# EP_project_Receiver.net
KiCad netlist of a schematic drawn in EAGLE
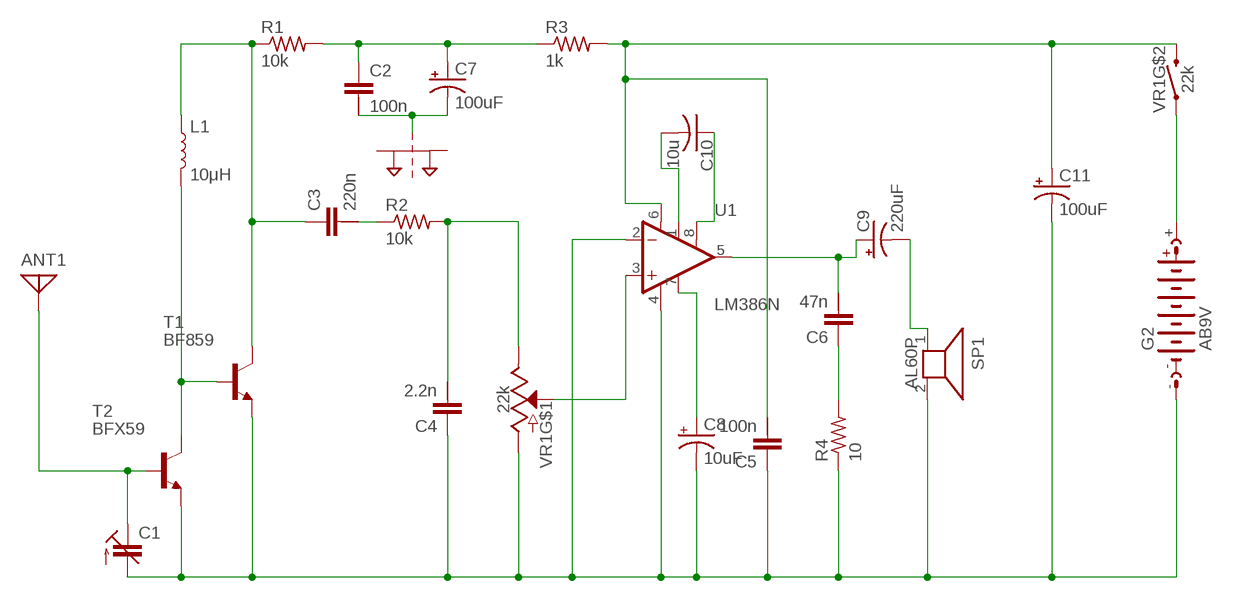
[diagram p0: schematic, sheet 1]

(export (version "E")
  (design (tool "Eeschema 10.0.6"))
  (components
    (comp (ref "ANT1")
      (value "ANTENNA")
      (footprint "eagle-import:PAD-01")
      (libsource (lib "eagle-import") (part "ANTENNA"))
    )
    (comp (ref "C1")
      (value "C-TRIMM808")
      (footprint "eagle-import:CTRIM808-BC")
      (libsource (lib "eagle-import") (part "C-TRIMM808"))
    )
    (comp (ref "C2")
      (value "100n")
      (footprint "eagle-import:C2.5_5-5")
      (libsource (lib "eagle-import") (part "C-2.5-5/5"))
    )
    (comp (ref "C3")
      (value "220n")
      (footprint "eagle-import:C2.5_5-5")
      (libsource (lib "eagle-import") (part "C-2.5-5/5"))
    )
    (comp (ref "C4")
      (value "2.2n")
      (footprint "eagle-import:C2.5_5-5")
      (libsource (lib "eagle-import") (part "C-2.5-5/5"))
    )
    (comp (ref "C5")
      (value "100n")
      (footprint "eagle-import:C2.5_5-5")
      (libsource (lib "eagle-import") (part "C-2.5-5/5"))
    )
    (comp (ref "C6")
      (value "47n")
      (footprint "eagle-import:C2.5_5-5")
      (libsource (lib "eagle-import") (part "C-2.5-5/5"))
    )
    (comp (ref "C7")
      (value "100uF")
      (footprint "eagle-import:PANASONIC_G")
      (libsource (lib "eagle-import") (part "560UF-PANASONIC_G-25V-20%"))
    )
    (comp (ref "C8")
      (value "10uF")
      (footprint "eagle-import:PANASONIC_G")
      (libsource (lib "eagle-import") (part "560UF-PANASONIC_G-25V-20%"))
    )
    (comp (ref "C9")
      (value "220uF")
      (footprint "eagle-import:PANASONIC_G")
      (libsource (lib "eagle-import") (part "560UF-PANASONIC_G-25V-20%"))
    )
    (comp (ref "C10")
      (value "10u")
      (footprint "eagle-import:C025-024X044")
      (libsource (lib "eagle-import") (part "C-US025-024X044"))
    )
    (comp (ref "C11")
      (value "100uF")
      (footprint "eagle-import:PANASONIC_G")
      (libsource (lib "eagle-import") (part "560UF-PANASONIC_G-25V-20%"))
    )
    (comp (ref "G2")
      (value "AB9V")
      (footprint "eagle-import:AB9V")
      (libsource (lib "eagle-import") (part "AB9V"))
    )
    (comp (ref "L1")
      (value "10μH")
      (footprint "eagle-import:0805")
      (libsource (lib "eagle-import") (part "10μH_SHIELDED_INDUCTOR0805"))
    )
    (comp (ref "R1")
      (value "10k")
      (footprint "eagle-import:0204_7")
      (libsource (lib "eagle-import") (part "R-US_0204/7"))
    )
    (comp (ref "R2")
      (value "10k")
      (footprint "eagle-import:0204_7")
      (libsource (lib "eagle-import") (part "R-US_0204/7"))
    )
    (comp (ref "R3")
      (value "1k")
      (footprint "eagle-import:0204_7")
      (libsource (lib "eagle-import") (part "R-US_0204/7"))
    )
    (comp (ref "R4")
      (value "10")
      (footprint "eagle-import:0204_7")
      (libsource (lib "eagle-import") (part "R-US_0204/7"))
    )
    (comp (ref "SP1")
      (value "AL60P")
      (footprint "eagle-import:AL60P")
      (libsource (lib "eagle-import") (part "AL60P"))
    )
    (comp (ref "SUPPLYTIE1")
      (value "2PT_GND_TIE")
      (footprint "eagle-import:2PT_GND_TIE")
      (libsource (lib "eagle-import") (part "2PT_GND_TIE"))
    )
    (comp (ref "T1")
      (value "BF859")
      (footprint "eagle-import:TO202")
      (libsource (lib "eagle-import") (part "BF859"))
    )
    (comp (ref "T2")
      (value "BFX59")
      (footprint "eagle-import:TO72")
      (libsource (lib "eagle-import") (part "BFX59"))
    )
    (comp (ref "U1")
      (value "LM386N")
      (footprint "eagle-import:DIP08")
      (libsource (lib "eagle-import") (part "LM386"))
    )
    (comp (ref "VR1")
      (value "22k")
      (footprint "eagle-import:POT-SWITCH-PTH")
      (libsource (lib "eagle-import") (part "POTENTIOMETER_W/SWITCHPOT_PTH_SWITCH"))
    )
  )
  (nets
    (net (code "1") (name "Net-(C1-A)") (class "Default")
      (node (ref "C1") (pin "2") (pinfunction "A_2") (pintype "passive"))
      (node (ref "C11") (pin "-") (pinfunction "-_-") (pintype "passive"))
      (node (ref "C4") (pin "1") (pinfunction "1_1") (pintype "passive"))
      (node (ref "C5") (pin "1") (pinfunction "1_1") (pintype "passive"))
      (node (ref "C8") (pin "-") (pinfunction "-_-") (pintype "passive"))
      (node (ref "G2") (pin "-") (pinfunction "-_-") (pintype "passive"))
      (node (ref "R4") (pin "1") (pinfunction "1_1") (pintype "passive"))
      (node (ref "SP1") (pin "2") (pinfunction "2_2") (pintype "passive"))
      (node (ref "T1") (pin "1") (pinfunction "E_1") (pintype "passive"))
      (node (ref "T2") (pin "1") (pinfunction "E_1") (pintype "passive"))
      (node (ref "U1") (pin "2") (pinfunction "-IN_2") (pintype "input"))
      (node (ref "U1") (pin "4") (pinfunction "V-_4") (pintype "power_in"))
      (node (ref "VR1") (pin "1") (pinfunction "A_1") (pintype "passive"))
    )
    (net (code "2") (name "Net-(C1-E)") (class "Default")
      (node (ref "ANT1") (pin "1") (pinfunction "1_1") (pintype "output"))
      (node (ref "C1") (pin "1") (pinfunction "E_1") (pintype "passive"))
      (node (ref "T2") (pin "2") (pinfunction "B_2") (pintype "passive"))
    )
    (net (code "3") (name "Net-(C2-Pad1)") (class "Default")
      (node (ref "C2") (pin "1") (pinfunction "1_1") (pintype "passive"))
      (node (ref "C7") (pin "+") (pinfunction "+_+") (pintype "passive"))
      (node (ref "R1") (pin "2") (pinfunction "2_2") (pintype "passive"))
      (node (ref "R3") (pin "1") (pinfunction "1_1") (pintype "passive"))
    )
    (net (code "4") (name "Net-(C2-Pad2)") (class "Default")
      (node (ref "C2") (pin "2") (pinfunction "2_2") (pintype "passive"))
      (node (ref "C7") (pin "-") (pinfunction "-_-") (pintype "passive"))
    )
    (net (code "5") (name "Net-(C3-Pad2)") (class "Default")
      (node (ref "C3") (pin "2") (pinfunction "2_2") (pintype "passive"))
      (node (ref "R2") (pin "1") (pinfunction "1_1") (pintype "passive"))
    )
    (net (code "6") (name "Net-(C6-Pad1)") (class "Default")
      (node (ref "C6") (pin "1") (pinfunction "1_1") (pintype "passive"))
      (node (ref "R4") (pin "2") (pinfunction "2_2") (pintype "passive"))
    )
    (net (code "7") (name "Net-(C9-Pad-)") (class "Default")
      (node (ref "C9") (pin "-") (pinfunction "-_-") (pintype "passive"))
      (node (ref "SP1") (pin "1") (pinfunction "1_1") (pintype "passive"))
    )
    (net (code "8") (name "Net-(C10-Pad1)") (class "Default")
      (node (ref "C10") (pin "1") (pinfunction "1_1") (pintype "passive"))
      (node (ref "U1") (pin "8") (pinfunction "GAIN_8") (pintype "bidirectional"))
    )
    (net (code "9") (name "Net-(C10-Pad2)") (class "Default")
      (node (ref "C10") (pin "2") (pinfunction "2_2") (pintype "passive"))
      (node (ref "U1") (pin "1") (pinfunction "GAIN_1") (pintype "bidirectional"))
    )
    (net (code "10") (name "Net-(T1-B)") (class "Default")
      (node (ref "L1") (pin "2") (pinfunction "2_2") (pintype "passive"))
      (node (ref "T1") (pin "3") (pinfunction "B_3") (pintype "passive"))
      (node (ref "T2") (pin "3") (pinfunction "C_3") (pintype "passive"))
    )
    (net (code "11") (name "Net-(T1-C)") (class "Default")
      (node (ref "C3") (pin "1") (pinfunction "1_1") (pintype "passive"))
      (node (ref "L1") (pin "1") (pinfunction "1_1") (pintype "passive"))
      (node (ref "R1") (pin "1") (pinfunction "1_1") (pintype "passive"))
      (node (ref "T1") (pin "2") (pinfunction "C_2") (pintype "passive"))
    )
    (net (code "12") (name "Net-(U1-+IN)") (class "Default")
      (node (ref "U1") (pin "3") (pinfunction "+IN_3") (pintype "input"))
      (node (ref "VR1") (pin "2") (pinfunction "S_2") (pintype "passive"))
    )
    (net (code "13") (name "Net-(U1-BP)") (class "Default")
      (node (ref "C8") (pin "+") (pinfunction "+_+") (pintype "passive"))
      (node (ref "U1") (pin "7") (pinfunction "BP_7") (pintype "bidirectional"))
    )
    (net (code "14") (name "Net-(U1-OUT)") (class "Default")
      (node (ref "C6") (pin "2") (pinfunction "2_2") (pintype "passive"))
      (node (ref "C9") (pin "+") (pinfunction "+_+") (pintype "passive"))
      (node (ref "U1") (pin "5") (pinfunction "OUT_5") (pintype "output"))
    )
    (net (code "15") (name "Net-(U1-V+)") (class "Default")
      (node (ref "C11") (pin "+") (pinfunction "+_+") (pintype "passive"))
      (node (ref "C5") (pin "2") (pinfunction "2_2") (pintype "passive"))
      (node (ref "R3") (pin "2") (pinfunction "2_2") (pintype "passive"))
      (node (ref "U1") (pin "6") (pinfunction "V+_6") (pintype "power_in"))
      (node (ref "VR1") (pin "S2") (pinfunction "2_S2") (pintype "passive"))
    )
    (net (code "16") (name "Net-(VR1A-E)") (class "Default")
      (node (ref "C4") (pin "2") (pinfunction "2_2") (pintype "passive"))
      (node (ref "R2") (pin "2") (pinfunction "2_2") (pintype "passive"))
      (node (ref "VR1") (pin "3") (pinfunction "E_3") (pintype "passive"))
    )
    (net (code "17") (name "Net-(VR1B-1)") (class "Default")
      (node (ref "G2") (pin "+") (pinfunction "+_+") (pintype "passive"))
      (node (ref "VR1") (pin "S1") (pinfunction "1_S1") (pintype "passive"))
    )
    (net (code "18") (name "unconnected-(C2-Pad3)") (class "Default")
      (node (ref "C2") (pin "3") (pinfunction "3_3") (pintype "passive"))
    )
    (net (code "19") (name "unconnected-(C3-Pad3)") (class "Default")
      (node (ref "C3") (pin "3") (pinfunction "3_3") (pintype "passive"))
    )
    (net (code "20") (name "unconnected-(C4-Pad3)") (class "Default")
      (node (ref "C4") (pin "3") (pinfunction "3_3") (pintype "passive"))
    )
    (net (code "21") (name "unconnected-(C5-Pad3)") (class "Default")
      (node (ref "C5") (pin "3") (pinfunction "3_3") (pintype "passive"))
    )
    (net (code "22") (name "unconnected-(C6-Pad3)") (class "Default")
      (node (ref "C6") (pin "3") (pinfunction "3_3") (pintype "passive"))
    )
    (net (code "23") (name "unconnected-(SUPPLYTIE1-PadP$1)") (class "Default")
      (node (ref "SUPPLYTIE1") (pin "P$1") (pinfunction "P$1_P$1") (pintype "bidirectional"))
    )
    (net (code "24") (name "unconnected-(SUPPLYTIE1-PadP$2)") (class "Default")
      (node (ref "SUPPLYTIE1") (pin "P$2") (pinfunction "P$2_P$2") (pintype "bidirectional"))
    )
  )
)
